# 14_pin_sop.net
KiCad netlist of a schematic drawn in EAGLE
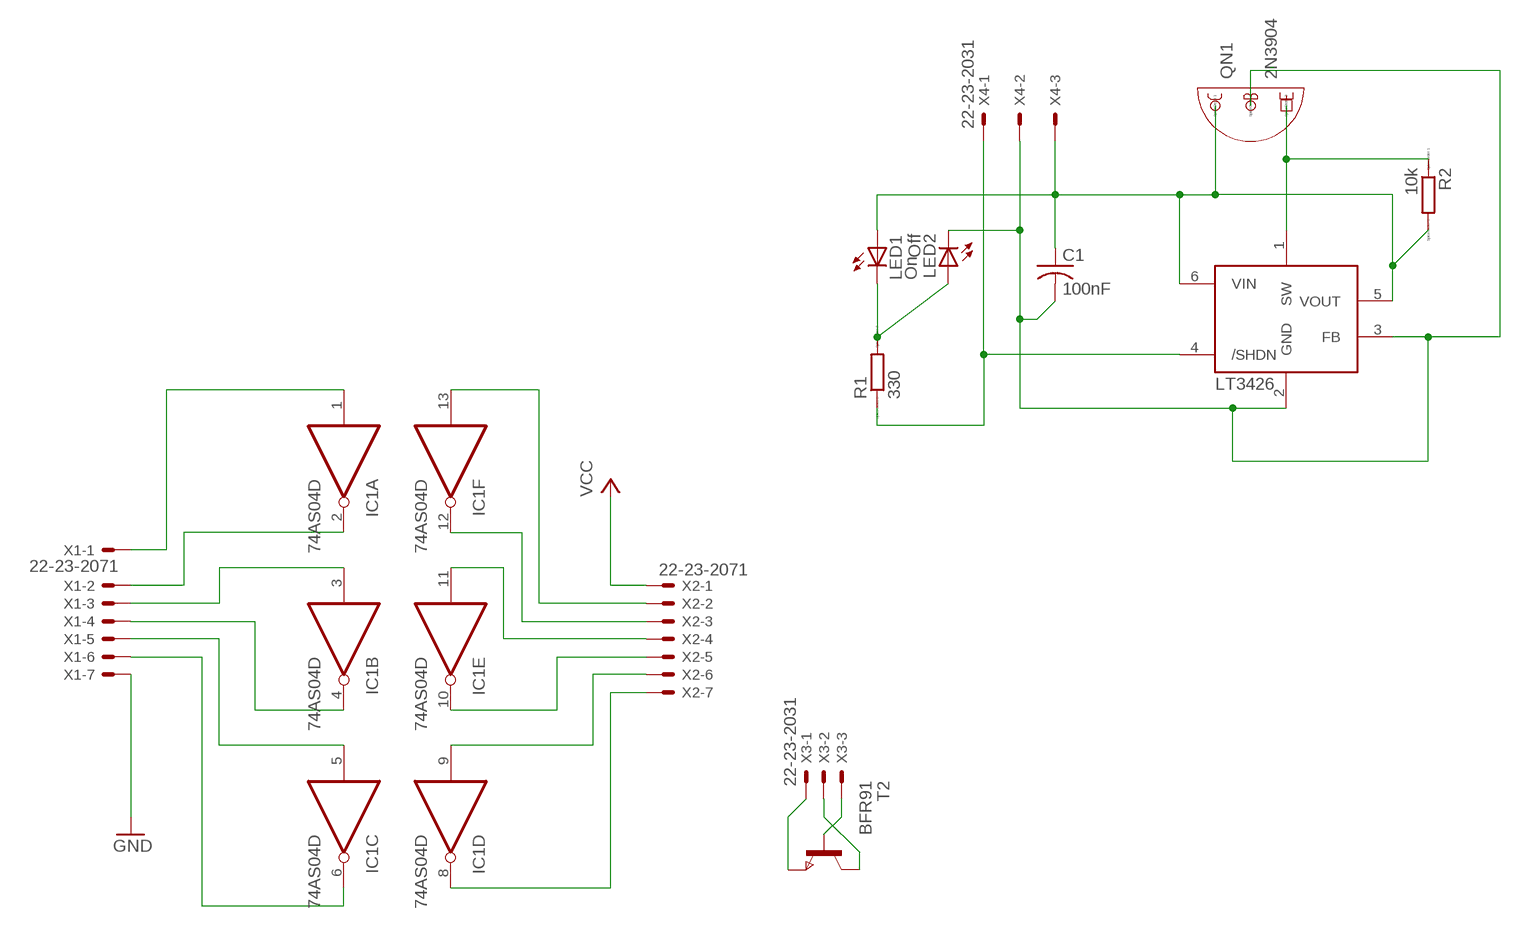
[diagram p0: schematic, sheet 1]

(export (version "E")
  (design (tool "Eeschema 10.0.6"))
  (components
    (comp (ref "C1")
      (value "100nF")
      (footprint "eagle-import:C1210")
      (libsource (lib "eagle-import") (part "C-USC1210"))
    )
    (comp (ref "IC1")
      (value "74AS04D")
      (footprint "eagle-import:SO14")
      (fields (field (name "OC_NEWARK") "unknown"))
      (libsource (lib "eagle-import") (part "7404DAS"))
    )
    (comp (ref "LED1")
      (value "On")
      (footprint "eagle-import:LED5MM")
      (libsource (lib "eagle-import") (part "LED5MM"))
    )
    (comp (ref "LED2")
      (value "Off")
      (footprint "eagle-import:LED5MM")
      (libsource (lib "eagle-import") (part "LED5MM"))
    )
    (comp (ref "QN1")
      (value "2N3904")
      (footprint "eagle-import:TO92")
      (libsource (lib "eagle-import") (part "2N3904"))
    )
    (comp (ref "R1")
      (value "330")
      (footprint "eagle-import:R0805")
      (libsource (lib "eagle-import") (part "R"))
    )
    (comp (ref "R2")
      (value "10k")
      (footprint "eagle-import:R0805")
      (libsource (lib "eagle-import") (part "R"))
    )
    (comp (ref "T2")
      (value "BFR91")
      (footprint "eagle-import:SOT323")
      (fields (field (name "MPN") "DSS4160U-7"))
      (libsource (lib "eagle-import") (part "NPNSOT323"))
    )
    (comp (ref "U$1")
      (value "LT3426")
      (footprint "eagle-import:SOT23-6")
      (libsource (lib "eagle-import") (part "LT3426"))
    )
    (comp (ref "X1")
      (value "22-23-2071")
      (footprint "eagle-import:22-23-2071")
      (fields (field (name "MF") "MOLEX"))
      (libsource (lib "eagle-import") (part "22-23-2071"))
    )
    (comp (ref "X2")
      (value "22-23-2071")
      (footprint "eagle-import:22-23-2071")
      (fields (field (name "MF") "MOLEX"))
      (libsource (lib "eagle-import") (part "22-23-2071"))
    )
    (comp (ref "X3")
      (value "22-23-2031")
      (footprint "eagle-import:22-23-2031")
      (fields (field (name "MF") "MOLEX"))
      (libsource (lib "eagle-import") (part "22-23-2031"))
    )
    (comp (ref "X4")
      (value "22-23-2031")
      (footprint "eagle-import:22-23-2031")
      (fields (field (name "MF") "MOLEX"))
      (libsource (lib "eagle-import") (part "22-23-2031"))
    )
  )
  (nets
    (net (code "1") (name "GND") (class "Default")
      (node (ref "C1") (pin "2") (pinfunction "2_2") (pintype "passive"))
      (node (ref "LED2") (pin "K") (pinfunction "C_K") (pintype "passive"))
      (node (ref "QN1") (pin "2") (pinfunction "B_2") (pintype "passive"))
      (node (ref "U$1") (pin "2") (pinfunction "GND_2") (pintype "power_in"))
      (node (ref "U$1") (pin "3") (pinfunction "FB_3") (pintype "input"))
      (node (ref "X1") (pin "7") (pinfunction "S_7") (pintype "passive"))
      (node (ref "X4") (pin "2") (pinfunction "S_2") (pintype "passive"))
    )
    (net (code "2") (name "Net-(IC1A-I)") (class "Default")
      (node (ref "IC1") (pin "1") (pinfunction "I_1") (pintype "input"))
      (node (ref "X1") (pin "1") (pinfunction "S_1") (pintype "passive"))
    )
    (net (code "3") (name "Net-(IC1A-O)") (class "Default")
      (node (ref "IC1") (pin "2") (pinfunction "O_2") (pintype "output"))
      (node (ref "X1") (pin "2") (pinfunction "S_2") (pintype "passive"))
    )
    (net (code "4") (name "Net-(IC1B-I)") (class "Default")
      (node (ref "IC1") (pin "3") (pinfunction "I_3") (pintype "input"))
      (node (ref "X1") (pin "3") (pinfunction "S_3") (pintype "passive"))
    )
    (net (code "5") (name "Net-(IC1B-O)") (class "Default")
      (node (ref "IC1") (pin "4") (pinfunction "O_4") (pintype "output"))
      (node (ref "X1") (pin "4") (pinfunction "S_4") (pintype "passive"))
    )
    (net (code "6") (name "Net-(IC1C-I)") (class "Default")
      (node (ref "IC1") (pin "5") (pinfunction "I_5") (pintype "input"))
      (node (ref "X1") (pin "5") (pinfunction "S_5") (pintype "passive"))
    )
    (net (code "7") (name "Net-(IC1C-O)") (class "Default")
      (node (ref "IC1") (pin "6") (pinfunction "O_6") (pintype "output"))
      (node (ref "X1") (pin "6") (pinfunction "S_6") (pintype "passive"))
    )
    (net (code "8") (name "Net-(IC1D-I)") (class "Default")
      (node (ref "IC1") (pin "9") (pinfunction "I_9") (pintype "input"))
      (node (ref "X2") (pin "6") (pinfunction "S_6") (pintype "passive"))
    )
    (net (code "9") (name "Net-(IC1D-O)") (class "Default")
      (node (ref "IC1") (pin "8") (pinfunction "O_8") (pintype "output"))
      (node (ref "X2") (pin "7") (pinfunction "S_7") (pintype "passive"))
    )
    (net (code "10") (name "Net-(IC1E-I)") (class "Default")
      (node (ref "IC1") (pin "11") (pinfunction "I_11") (pintype "input"))
      (node (ref "X2") (pin "4") (pinfunction "S_4") (pintype "passive"))
    )
    (net (code "11") (name "Net-(IC1E-O)") (class "Default")
      (node (ref "IC1") (pin "10") (pinfunction "O_10") (pintype "output"))
      (node (ref "X2") (pin "5") (pinfunction "S_5") (pintype "passive"))
    )
    (net (code "12") (name "Net-(IC1F-I)") (class "Default")
      (node (ref "IC1") (pin "13") (pinfunction "I_13") (pintype "input"))
      (node (ref "X2") (pin "2") (pinfunction "S_2") (pintype "passive"))
    )
    (net (code "13") (name "Net-(IC1F-O)") (class "Default")
      (node (ref "IC1") (pin "12") (pinfunction "O_12") (pintype "output"))
      (node (ref "X2") (pin "3") (pinfunction "S_3") (pintype "passive"))
    )
    (net (code "14") (name "Net-(LED1-C)") (class "Default")
      (node (ref "LED1") (pin "K") (pinfunction "C_K") (pintype "passive"))
      (node (ref "LED2") (pin "A") (pinfunction "A_A") (pintype "passive"))
      (node (ref "R1") (pin "2") (pinfunction "2_2") (pintype "passive"))
    )
    (net (code "15") (name "Net-(QN1-C)") (class "Default")
      (node (ref "C1") (pin "1") (pinfunction "1_1") (pintype "passive"))
      (node (ref "LED1") (pin "A") (pinfunction "A_A") (pintype "passive"))
      (node (ref "QN1") (pin "1") (pinfunction "C_1") (pintype "passive"))
      (node (ref "R2") (pin "2") (pinfunction "2_2") (pintype "passive"))
      (node (ref "U$1") (pin "5") (pinfunction "VOUT_5") (pintype "output"))
      (node (ref "U$1") (pin "6") (pinfunction "VIN_6") (pintype "input"))
      (node (ref "X4") (pin "3") (pinfunction "S_3") (pintype "passive"))
    )
    (net (code "16") (name "Net-(QN1-E)") (class "Default")
      (node (ref "QN1") (pin "3") (pinfunction "E_3") (pintype "passive"))
      (node (ref "R2") (pin "1") (pinfunction "1_1") (pintype "passive"))
      (node (ref "U$1") (pin "1") (pinfunction "SW_1") (pintype "output"))
    )
    (net (code "17") (name "Net-(T2-B)") (class "Default")
      (node (ref "T2") (pin "2") (pinfunction "B_2") (pintype "passive"))
      (node (ref "X3") (pin "3") (pinfunction "S_3") (pintype "passive"))
    )
    (net (code "18") (name "Net-(T2-C)") (class "Default")
      (node (ref "T2") (pin "1") (pinfunction "C_1") (pintype "passive"))
      (node (ref "X3") (pin "2") (pinfunction "S_2") (pintype "passive"))
    )
    (net (code "19") (name "Net-(T2-E)") (class "Default")
      (node (ref "T2") (pin "3") (pinfunction "E_3") (pintype "passive"))
      (node (ref "X3") (pin "1") (pinfunction "S_1") (pintype "passive"))
    )
    (net (code "20") (name "Net-(U$1-{slash}SHDN)") (class "Default")
      (node (ref "R1") (pin "1") (pinfunction "1_1") (pintype "passive"))
      (node (ref "U$1") (pin "4") (pinfunction "/SHDN_4") (pintype "input"))
      (node (ref "X4") (pin "1") (pinfunction "S_1") (pintype "passive"))
    )
    (net (code "21") (name "VCC") (class "Default")
      (node (ref "X2") (pin "1") (pinfunction "S_1") (pintype "passive"))
    )
  )
)
